# GND_PCB_Data_Conversion.net
KiCad netlist of a schematic drawn in Altium Designer
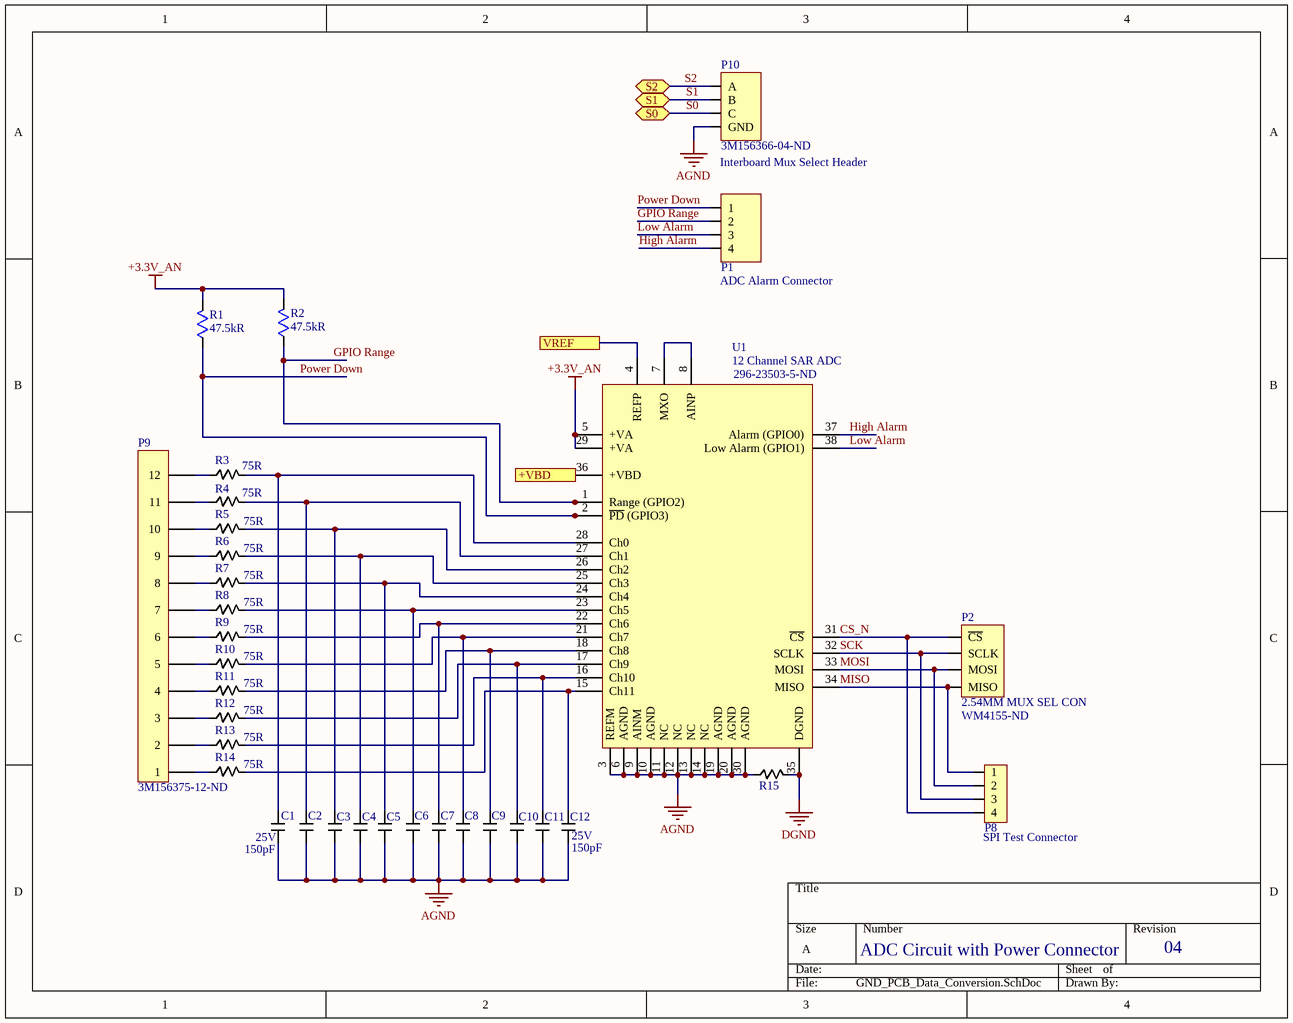
[diagram p0: GND_PCB_Data_Conversion.SchDoc]

(export (version "E")
  (design (tool "Eeschema 10.0.6"))
  (components
    (comp (ref "C1")
      (value "150PF Charge Res Caps")
      (footprint "150PF Cap Charge Resevoir")
      (description "Charge Res Caps for ADC input channels")
      (fields
        (field (name "MANUFACTURER") "KEMET")
        (field (name "MANUFACTURER PART NUMBER") "C0402C151J3GAC7867")
        (field (name "CAPACITANCE") "150pF")
        (field (name "VOLTAGE RATING") "25V")
      )
      (libsource (lib "Schematic_Library") (part "150PF Charge Res Caps"))
    )
    (comp (ref "C2")
      (value "150PF Charge Res Caps")
      (footprint "150PF Cap Charge Resevoir")
      (description "Charge Res Caps for ADC input channels")
      (fields
        (field (name "MANUFACTURER") "KEMET")
        (field (name "MANUFACTURER PART NUMBER") "C0402C151J3GAC7867")
      )
      (libsource (lib "Schematic_Library") (part "150PF Charge Res Caps"))
    )
    (comp (ref "C3")
      (value "150PF Charge Res Caps")
      (footprint "150PF Cap Charge Resevoir")
      (description "Charge Res Caps for ADC input channels")
      (fields
        (field (name "MANUFACTURER") "KEMET")
        (field (name "MANUFACTURER PART NUMBER") "C0402C151J3GAC7867")
      )
      (libsource (lib "Schematic_Library") (part "150PF Charge Res Caps"))
    )
    (comp (ref "C4")
      (value "150PF Charge Res Caps")
      (footprint "150PF Cap Charge Resevoir")
      (description "Charge Res Caps for ADC input channels")
      (fields
        (field (name "MANUFACTURER") "KEMET")
        (field (name "MANUFACTURER PART NUMBER") "C0402C151J3GAC7867")
      )
      (libsource (lib "Schematic_Library") (part "150PF Charge Res Caps"))
    )
    (comp (ref "C5")
      (value "150PF Charge Res Caps")
      (footprint "150PF Cap Charge Resevoir")
      (description "Charge Res Caps for ADC input channels")
      (fields
        (field (name "MANUFACTURER") "KEMET")
        (field (name "MANUFACTURER PART NUMBER") "C0402C151J3GAC7867")
      )
      (libsource (lib "Schematic_Library") (part "150PF Charge Res Caps"))
    )
    (comp (ref "C6")
      (value "150PF Charge Res Caps")
      (footprint "150PF Cap Charge Resevoir")
      (description "Charge Res Caps for ADC input channels")
      (fields
        (field (name "MANUFACTURER") "KEMET")
        (field (name "MANUFACTURER PART NUMBER") "C0402C151J3GAC7867")
      )
      (libsource (lib "Schematic_Library") (part "150PF Charge Res Caps"))
    )
    (comp (ref "C7")
      (value "150PF Charge Res Caps")
      (footprint "150PF Cap Charge Resevoir")
      (description "Charge Res Caps for ADC input channels")
      (fields
        (field (name "MANUFACTURER") "KEMET")
        (field (name "MANUFACTURER PART NUMBER") "C0402C151J3GAC7867")
      )
      (libsource (lib "Schematic_Library") (part "150PF Charge Res Caps"))
    )
    (comp (ref "C8")
      (value "150PF Charge Res Caps")
      (footprint "150PF Cap Charge Resevoir")
      (description "Charge Res Caps for ADC input channels")
      (fields
        (field (name "MANUFACTURER") "KEMET")
        (field (name "MANUFACTURER PART NUMBER") "C0402C151J3GAC7867")
      )
      (libsource (lib "Schematic_Library") (part "150PF Charge Res Caps"))
    )
    (comp (ref "C9")
      (value "150PF Charge Res Caps")
      (footprint "150PF Cap Charge Resevoir")
      (description "Charge Res Caps for ADC input channels")
      (fields
        (field (name "MANUFACTURER") "KEMET")
        (field (name "MANUFACTURER PART NUMBER") "C0402C151J3GAC7867")
      )
      (libsource (lib "Schematic_Library") (part "150PF Charge Res Caps"))
    )
    (comp (ref "C10")
      (value "150PF Charge Res Caps")
      (footprint "150PF Cap Charge Resevoir")
      (description "Charge Res Caps for ADC input channels")
      (fields
        (field (name "MANUFACTURER") "KEMET")
        (field (name "MANUFACTURER PART NUMBER") "C0402C151J3GAC7867")
      )
      (libsource (lib "Schematic_Library") (part "150PF Charge Res Caps"))
    )
    (comp (ref "C11")
      (value "150PF Charge Res Caps")
      (footprint "150PF Cap Charge Resevoir")
      (description "Charge Res Caps for ADC input channels")
      (fields
        (field (name "MANUFACTURER") "KEMET")
        (field (name "MANUFACTURER PART NUMBER") "C0402C151J3GAC7867")
      )
      (libsource (lib "Schematic_Library") (part "150PF Charge Res Caps"))
    )
    (comp (ref "C12")
      (value "150PF Charge Res Caps")
      (footprint "150PF Cap Charge Resevoir")
      (description "Charge Res Caps for ADC input channels")
      (fields
        (field (name "MANUFACTURER") "KEMET")
        (field (name "MANUFACTURER PART NUMBER") "C0402C151J3GAC7867")
        (field (name "CAPACITANCE") "150pF")
        (field (name "VOLTAGE RATING") "25V")
      )
      (libsource (lib "Schematic_Library") (part "150PF Charge Res Caps"))
    )
    (comp (ref "P1")
      (value "4 pos ADC Alarm Header")
      (footprint "4POS 2.54MM HEADER MUX SEL")
      (description "Connector Header Through Hole, Right Angle 4 position 0.100\" (2.54mm)")
      (fields (field (name "MANUFACTURER") "Molex") (field (name "MANUFACTURER PART NUMBER") "0705530108"))
      (libsource (lib "Schematic_Library") (part "4 pos ADC Alarm Header"))
    )
    (comp (ref "P2")
      (value "2.54MM MUX SEL CON")
      (footprint "4POS 2.54MM HEADER MUX SEL")
      (description "SPI Connector")
      (fields
        (field (name "MANUFACTURER") "Molex")
        (field (name "MANUFACTURER PART NUMBER") "0705530108")
        (field (name "SUPPLIER PART NUMBER 1") "WM4155-ND")
      )
      (libsource (lib "Schematic_Library") (part "2.54MM MUX SEL CON"))
    )
    (comp (ref "P8")
      (value "4POS SPI Test Connector Header Pin")
      (footprint "4POS SPI Test Connector")
      (description "Connector Header Through Hole, Right Angle 4 position 0.100\" (2.54mm)")
      (fields
        (field (name "MANUFACTURER") "TE Connectivity")
        (field (name "MANUFACTURER PART NUMBER") "640455-4")
      )
      (libsource (lib "Schematic_Library") (part "4POS SPI Test Connector Header Pin"))
    )
    (comp (ref "P9")
      (value "12POS Dual Header W/O 3D Body")
      (footprint "12POS Dual Header W/0 3D Body")
      (description "Connector Header Through Hole 12 position 0.100\" (2.54mm)")
      (fields
        (field (name "MANUFACTURER") "3M")
        (field (name "MANUFACTURER PART NUMBER") "929715-06-06-EU")
        (field (name "SUPPLIER PART NUMBER 1") "3M156375-12-ND")
      )
      (libsource (lib "Schematic_Library") (part "12POS Dual Header W/O 3D Body"))
    )
    (comp (ref "P10")
      (value "Mux Select Interboard Header")
      (footprint "Mux Select Interboard Connector")
      (description "Connector Header Through Hole 4 position 0.100\" (2.54mm)")
      (fields
        (field (name "MANUFACTURER") "3M")
        (field (name "MANUFACTURER PART NUMBER") "929710-06-02-RK")
        (field (name "SUPPLIER PART NUMBER 1") "3M156366-04-ND")
      )
      (libsource (lib "Schematic_Library") (part "Mux Select Interboard Header"))
    )
    (comp (ref "R1")
      (value "Green")
      (footprint "Green_LED_Resistor_90.9")
      (description "RES 47.5K OHM 0.5% 1/10W 0603")
      (fields
        (field (name "MANUFACTURER") "Stackpole Electronics")
        (field (name "MANUFACTURER PART NUMBER") "RNCF0603DTE47K5")
        (field (name "RESISTANCE") "47.5kR")
      )
      (libsource (lib "Schematic_Library") (part "47.5k PullUp RES ADC"))
    )
    (comp (ref "R2")
      (value "47.5k PullUp RES ADC")
      (footprint "0603_MD_RES")
      (description "RES 47.5K OHM 0.5% 1/10W 0603")
      (fields
        (field (name "MANUFACTURER") "Stackpole Electronics")
        (field (name "MANUFACTURER PART NUMBER") "RNCF0603DTE47K5")
        (field (name "RESISTANCE") "47.5kR")
      )
      (libsource (lib "Schematic_Library") (part "47.5k PullUp RES ADC"))
    )
    (comp (ref "R3")
      (value "75 Ohm Charge Resevoir Resistor")
      (footprint "Chip2PinSM127P600-8N")
      (fields
        (field (name "MANUFACTURER") "Rohm")
        (field (name "MANUFACTURER PART NUMBER") "KTR03EZPF75R0")
        (field (name "TOLERANCE") "1%")
        (field (name "RESISTANCE") "75R")
      )
      (libsource (lib "Schematic_Library") (part "75 Ohm Charge Resevoir Resistor"))
    )
    (comp (ref "R4")
      (value "75 Ohm Charge Resevoir Resistor")
      (footprint "Chip2PinSM127P600-8N")
      (fields
        (field (name "MANUFACTURER") "Rohm")
        (field (name "MANUFACTURER PART NUMBER") "KTR03EZPF75R0")
        (field (name "TOLERANCE") "1%")
        (field (name "RESISTANCE") "75R")
      )
      (libsource (lib "Schematic_Library") (part "75 Ohm Charge Resevoir Resistor"))
    )
    (comp (ref "R5")
      (value "75 Ohm Charge Resevoir Resistor")
      (footprint "Chip2PinSM127P600-8N")
      (fields
        (field (name "MANUFACTURER") "Rohm")
        (field (name "MANUFACTURER PART NUMBER") "KTR03EZPF75R0")
        (field (name "TOLERANCE") "1%")
        (field (name "RESISTANCE") "75R")
      )
      (libsource (lib "Schematic_Library") (part "75 Ohm Charge Resevoir Resistor"))
    )
    (comp (ref "R6")
      (value "75 Ohm Charge Resevoir Resistor")
      (footprint "Chip2PinSM127P600-8N")
      (fields
        (field (name "MANUFACTURER") "Rohm")
        (field (name "MANUFACTURER PART NUMBER") "KTR03EZPF75R0")
        (field (name "TOLERANCE") "1%")
        (field (name "RESISTANCE") "75R")
      )
      (libsource (lib "Schematic_Library") (part "75 Ohm Charge Resevoir Resistor"))
    )
    (comp (ref "R7")
      (value "75 Ohm Charge Resevoir Resistor")
      (footprint "Chip2PinSM127P600-8N")
      (fields
        (field (name "MANUFACTURER") "Rohm")
        (field (name "MANUFACTURER PART NUMBER") "KTR03EZPF75R0")
        (field (name "TOLERANCE") "1%")
        (field (name "RESISTANCE") "75R")
      )
      (libsource (lib "Schematic_Library") (part "75 Ohm Charge Resevoir Resistor"))
    )
    (comp (ref "R8")
      (value "75 Ohm Charge Resevoir Resistor")
      (footprint "Chip2PinSM127P600-8N")
      (fields
        (field (name "MANUFACTURER") "Rohm")
        (field (name "MANUFACTURER PART NUMBER") "KTR03EZPF75R0")
        (field (name "TOLERANCE") "1%")
        (field (name "RESISTANCE") "75R")
      )
      (libsource (lib "Schematic_Library") (part "75 Ohm Charge Resevoir Resistor"))
    )
    (comp (ref "R9")
      (value "75 Ohm Charge Resevoir Resistor")
      (footprint "Chip2PinSM127P600-8N")
      (fields
        (field (name "MANUFACTURER") "Rohm")
        (field (name "MANUFACTURER PART NUMBER") "KTR03EZPF75R0")
        (field (name "TOLERANCE") "1%")
        (field (name "RESISTANCE") "75R")
      )
      (libsource (lib "Schematic_Library") (part "75 Ohm Charge Resevoir Resistor"))
    )
    (comp (ref "R10")
      (value "75 Ohm Charge Resevoir Resistor")
      (footprint "Chip2PinSM127P600-8N")
      (fields
        (field (name "MANUFACTURER") "Rohm")
        (field (name "MANUFACTURER PART NUMBER") "KTR03EZPF75R0")
        (field (name "TOLERANCE") "1%")
        (field (name "RESISTANCE") "75R")
      )
      (libsource (lib "Schematic_Library") (part "75 Ohm Charge Resevoir Resistor"))
    )
    (comp (ref "R11")
      (value "75 Ohm Charge Resevoir Resistor")
      (footprint "Chip2PinSM127P600-8N")
      (fields
        (field (name "MANUFACTURER") "Rohm")
        (field (name "MANUFACTURER PART NUMBER") "KTR03EZPF75R0")
        (field (name "TOLERANCE") "1%")
        (field (name "RESISTANCE") "75R")
      )
      (libsource (lib "Schematic_Library") (part "75 Ohm Charge Resevoir Resistor"))
    )
    (comp (ref "R12")
      (value "75 Ohm Charge Resevoir Resistor")
      (footprint "Chip2PinSM127P600-8N")
      (fields
        (field (name "MANUFACTURER") "Rohm")
        (field (name "MANUFACTURER PART NUMBER") "KTR03EZPF75R0")
        (field (name "TOLERANCE") "1%")
        (field (name "RESISTANCE") "75R")
      )
      (libsource (lib "Schematic_Library") (part "75 Ohm Charge Resevoir Resistor"))
    )
    (comp (ref "R13")
      (value "75 Ohm Charge Resevoir Resistor")
      (footprint "Chip2PinSM127P600-8N")
      (fields
        (field (name "MANUFACTURER") "Rohm")
        (field (name "MANUFACTURER PART NUMBER") "KTR03EZPF75R0")
        (field (name "TOLERANCE") "1%")
        (field (name "RESISTANCE") "75R")
      )
      (libsource (lib "Schematic_Library") (part "75 Ohm Charge Resevoir Resistor"))
    )
    (comp (ref "R14")
      (value "75 Ohm Charge Resevoir Resistor")
      (footprint "Chip2PinSM127P600-8N")
      (fields
        (field (name "MANUFACTURER") "Rohm")
        (field (name "MANUFACTURER PART NUMBER") "KTR03EZPF75R0")
        (field (name "TOLERANCE") "1%")
        (field (name "RESISTANCE") "75R")
      )
      (libsource (lib "Schematic_Library") (part "75 Ohm Charge Resevoir Resistor"))
    )
    (comp (ref "R15")
      (value "0 Ohm Resistor")
      (footprint "0 Ohm Resistor")
      (description "0 Ohm Resistor for connecting polygon pours")
      (libsource (lib "Schematic_Library") (part "0 Ohm Resistor"))
    )
    (comp (ref "U1")
      (value "12 Channel SAR ADC")
      (footprint "12 Channel SAR ADC")
      (description "12 Bit SAR ADC")
      (fields
        (field (name "MANUFACTURER") "Texas Instruments")
        (field (name "MANUFACTURER PART NUMBER") "ADS7952SDBT")
        (field (name "SUPPLIER PART NUMBER 1") "296-23503-5-ND")
      )
      (libsource (lib "Schematic_Library") (part "12 Channel SAR ADC"))
    )
  )
  (nets
    (net (code "1") (name "+3.3V_AN") (class "Default")
      (node (ref "R1") (pin "2") (pinfunction "2_2") (pintype "passive"))
      (node (ref "R2") (pin "2") (pinfunction "2_2") (pintype "passive"))
      (node (ref "U1") (pin "29") (pinfunction "+VA_29") (pintype "passive"))
      (node (ref "U1") (pin "5") (pinfunction "+VA_5") (pintype "passive"))
    )
    (net (code "2") (name "/+VBD") (class "Default")
      (node (ref "U1") (pin "36") (pinfunction "+VBD_36") (pintype "passive"))
    )
    (net (code "3") (name "/CS_N") (class "Default")
      (node (ref "P2") (pin "4") (pinfunction "~{CS}_4") (pintype "passive"))
      (node (ref "P8") (pin "4") (pinfunction "4_4") (pintype "passive"))
      (node (ref "U1") (pin "31") (pinfunction "~{CS}_31") (pintype "passive"))
    )
    (net (code "4") (name "/GPIO Range") (class "Default")
      (node (ref "P1") (pin "2") (pinfunction "2_2") (pintype "passive"))
      (node (ref "R2") (pin "1") (pinfunction "1_1") (pintype "passive"))
      (node (ref "U1") (pin "1") (pinfunction "Range_(GPIO2)_1") (pintype "passive"))
    )
    (net (code "5") (name "/High Alarm") (class "Default")
      (node (ref "P1") (pin "4") (pinfunction "4_4") (pintype "passive"))
      (node (ref "U1") (pin "37") (pinfunction "Alarm_(GPIO0)_37") (pintype "passive"))
    )
    (net (code "6") (name "/Low Alarm") (class "Default")
      (node (ref "P1") (pin "3") (pinfunction "3_3") (pintype "passive"))
      (node (ref "U1") (pin "38") (pinfunction "Low_Alarm_(GPIO1)_38") (pintype "passive"))
    )
    (net (code "7") (name "/MISO") (class "Default")
      (node (ref "P2") (pin "1") (pinfunction "MISO_1") (pintype "passive"))
      (node (ref "P8") (pin "1") (pinfunction "1_1") (pintype "passive"))
      (node (ref "U1") (pin "34") (pinfunction "MISO_34") (pintype "passive"))
    )
    (net (code "8") (name "/MOSI") (class "Default")
      (node (ref "P2") (pin "2") (pinfunction "MOSI_2") (pintype "passive"))
      (node (ref "P8") (pin "2") (pinfunction "2_2") (pintype "passive"))
      (node (ref "U1") (pin "33") (pinfunction "MOSI_33") (pintype "passive"))
    )
    (net (code "9") (name "/Power Down") (class "Default")
      (node (ref "P1") (pin "1") (pinfunction "1_1") (pintype "passive"))
      (node (ref "R1") (pin "1") (pinfunction "1_1") (pintype "passive"))
      (node (ref "U1") (pin "2") (pinfunction "~{PD}_(GPIO3)_2") (pintype "passive"))
    )
    (net (code "10") (name "/S0") (class "Default")
      (node (ref "P10") (pin "3") (pinfunction "C_3") (pintype "passive"))
    )
    (net (code "11") (name "/S1") (class "Default")
      (node (ref "P10") (pin "2") (pinfunction "B_2") (pintype "passive"))
    )
    (net (code "12") (name "/S2") (class "Default")
      (node (ref "P10") (pin "1") (pinfunction "A_1") (pintype "passive"))
    )
    (net (code "13") (name "/SCK") (class "Default")
      (node (ref "P2") (pin "3") (pinfunction "SCLK_3") (pintype "passive"))
      (node (ref "P8") (pin "3") (pinfunction "3_3") (pintype "passive"))
      (node (ref "U1") (pin "32") (pinfunction "SCLK_32") (pintype "passive"))
    )
    (net (code "14") (name "/VREF") (class "Default")
      (node (ref "U1") (pin "4") (pinfunction "REFP_4") (pintype "passive"))
    )
    (net (code "15") (name "AGND") (class "Default")
      (node (ref "C1") (pin "1") (pinfunction "1_1") (pintype "passive"))
      (node (ref "C10") (pin "1") (pinfunction "1_1") (pintype "passive"))
      (node (ref "C11") (pin "1") (pinfunction "1_1") (pintype "passive"))
      (node (ref "C12") (pin "1") (pinfunction "1_1") (pintype "passive"))
      (node (ref "C2") (pin "1") (pinfunction "1_1") (pintype "passive"))
      (node (ref "C3") (pin "1") (pinfunction "1_1") (pintype "passive"))
      (node (ref "C4") (pin "1") (pinfunction "1_1") (pintype "passive"))
      (node (ref "C5") (pin "1") (pinfunction "1_1") (pintype "passive"))
      (node (ref "C6") (pin "1") (pinfunction "1_1") (pintype "passive"))
      (node (ref "C7") (pin "1") (pinfunction "1_1") (pintype "passive"))
      (node (ref "C8") (pin "1") (pinfunction "1_1") (pintype "passive"))
      (node (ref "C9") (pin "1") (pinfunction "1_1") (pintype "passive"))
      (node (ref "P10") (pin "4") (pinfunction "GND_4") (pintype "passive"))
      (node (ref "R15") (pin "1") (pinfunction "1_1") (pintype "passive"))
      (node (ref "U1") (pin "10") (pinfunction "AGND_10") (pintype "passive"))
      (node (ref "U1") (pin "11") (pinfunction "NC_11") (pintype "passive"))
      (node (ref "U1") (pin "12") (pinfunction "NC_12") (pintype "passive"))
      (node (ref "U1") (pin "13") (pinfunction "NC_13") (pintype "passive"))
      (node (ref "U1") (pin "14") (pinfunction "NC_14") (pintype "passive"))
      (node (ref "U1") (pin "19") (pinfunction "AGND_19") (pintype "passive"))
      (node (ref "U1") (pin "20") (pinfunction "AGND_20") (pintype "passive"))
      (node (ref "U1") (pin "3") (pinfunction "REFM_3") (pintype "passive"))
      (node (ref "U1") (pin "30") (pinfunction "AGND_30") (pintype "passive"))
      (node (ref "U1") (pin "6") (pinfunction "AGND_6") (pintype "passive"))
      (node (ref "U1") (pin "9") (pinfunction "AINM_9") (pintype "passive"))
    )
    (net (code "16") (name "DGND") (class "Default")
      (node (ref "R15") (pin "2") (pinfunction "2_2") (pintype "passive"))
      (node (ref "U1") (pin "35") (pinfunction "DGND_35") (pintype "passive"))
    )
    (net (code "17") (name "Net-(P9-Pad1)") (class "Default")
      (node (ref "P9") (pin "1") (pinfunction "1_1") (pintype "passive"))
      (node (ref "R14") (pin "1") (pinfunction "1_1") (pintype "passive"))
    )
    (net (code "18") (name "Net-(P9-Pad2)") (class "Default")
      (node (ref "P9") (pin "2") (pinfunction "2_2") (pintype "passive"))
      (node (ref "R13") (pin "1") (pinfunction "1_1") (pintype "passive"))
    )
    (net (code "19") (name "Net-(P9-Pad3)") (class "Default")
      (node (ref "P9") (pin "3") (pinfunction "3_3") (pintype "passive"))
      (node (ref "R12") (pin "1") (pinfunction "1_1") (pintype "passive"))
    )
    (net (code "20") (name "Net-(P9-Pad4)") (class "Default")
      (node (ref "P9") (pin "4") (pinfunction "4_4") (pintype "passive"))
      (node (ref "R11") (pin "1") (pinfunction "1_1") (pintype "passive"))
    )
    (net (code "21") (name "Net-(P9-Pad5)") (class "Default")
      (node (ref "P9") (pin "5") (pinfunction "5_5") (pintype "passive"))
      (node (ref "R10") (pin "1") (pinfunction "1_1") (pintype "passive"))
    )
    (net (code "22") (name "Net-(P9-Pad6)") (class "Default")
      (node (ref "P9") (pin "6") (pinfunction "6_6") (pintype "passive"))
      (node (ref "R9") (pin "1") (pinfunction "1_1") (pintype "passive"))
    )
    (net (code "23") (name "Net-(P9-Pad7)") (class "Default")
      (node (ref "P9") (pin "7") (pinfunction "7_7") (pintype "passive"))
      (node (ref "R8") (pin "1") (pinfunction "1_1") (pintype "passive"))
    )
    (net (code "24") (name "Net-(P9-Pad8)") (class "Default")
      (node (ref "P9") (pin "8") (pinfunction "8_8") (pintype "passive"))
      (node (ref "R7") (pin "1") (pinfunction "1_1") (pintype "passive"))
    )
    (net (code "25") (name "Net-(P9-Pad9)") (class "Default")
      (node (ref "P9") (pin "9") (pinfunction "9_9") (pintype "passive"))
      (node (ref "R6") (pin "1") (pinfunction "1_1") (pintype "passive"))
    )
    (net (code "26") (name "Net-(P9-Pad10)") (class "Default")
      (node (ref "P9") (pin "10") (pinfunction "10_10") (pintype "passive"))
      (node (ref "R5") (pin "1") (pinfunction "1_1") (pintype "passive"))
    )
    (net (code "27") (name "Net-(P9-Pad11)") (class "Default")
      (node (ref "P9") (pin "11") (pinfunction "11_11") (pintype "passive"))
      (node (ref "R4") (pin "1") (pinfunction "1_1") (pintype "passive"))
    )
    (net (code "28") (name "Net-(P9-Pad12)") (class "Default")
      (node (ref "P9") (pin "12") (pinfunction "12_12") (pintype "passive"))
      (node (ref "R3") (pin "1") (pinfunction "1_1") (pintype "passive"))
    )
    (net (code "29") (name "Net-(U1-AINP)") (class "Default")
      (node (ref "U1") (pin "7") (pinfunction "MXO_7") (pintype "passive"))
      (node (ref "U1") (pin "8") (pinfunction "AINP_8") (pintype "passive"))
    )
    (net (code "30") (name "Net-(U1-Ch0)") (class "Default")
      (node (ref "C1") (pin "2") (pinfunction "2_2") (pintype "passive"))
      (node (ref "R3") (pin "2") (pinfunction "2_2") (pintype "passive"))
      (node (ref "U1") (pin "28") (pinfunction "Ch0_28") (pintype "passive"))
    )
    (net (code "31") (name "Net-(U1-Ch1)") (class "Default")
      (node (ref "C2") (pin "2") (pinfunction "2_2") (pintype "passive"))
      (node (ref "R4") (pin "2") (pinfunction "2_2") (pintype "passive"))
      (node (ref "U1") (pin "27") (pinfunction "Ch1_27") (pintype "passive"))
    )
    (net (code "32") (name "Net-(U1-Ch2)") (class "Default")
      (node (ref "C3") (pin "2") (pinfunction "2_2") (pintype "passive"))
      (node (ref "R5") (pin "2") (pinfunction "2_2") (pintype "passive"))
      (node (ref "U1") (pin "26") (pinfunction "Ch2_26") (pintype "passive"))
    )
    (net (code "33") (name "Net-(U1-Ch3)") (class "Default")
      (node (ref "C4") (pin "2") (pinfunction "2_2") (pintype "passive"))
      (node (ref "R6") (pin "2") (pinfunction "2_2") (pintype "passive"))
      (node (ref "U1") (pin "25") (pinfunction "Ch3_25") (pintype "passive"))
    )
    (net (code "34") (name "Net-(U1-Ch4)") (class "Default")
      (node (ref "C5") (pin "2") (pinfunction "2_2") (pintype "passive"))
      (node (ref "R7") (pin "2") (pinfunction "2_2") (pintype "passive"))
      (node (ref "U1") (pin "24") (pinfunction "Ch4_24") (pintype "passive"))
    )
    (net (code "35") (name "Net-(U1-Ch5)") (class "Default")
      (node (ref "C6") (pin "2") (pinfunction "2_2") (pintype "passive"))
      (node (ref "R8") (pin "2") (pinfunction "2_2") (pintype "passive"))
      (node (ref "U1") (pin "23") (pinfunction "Ch5_23") (pintype "passive"))
    )
    (net (code "36") (name "Net-(U1-Ch6)") (class "Default")
      (node (ref "C7") (pin "2") (pinfunction "2_2") (pintype "passive"))
      (node (ref "R9") (pin "2") (pinfunction "2_2") (pintype "passive"))
      (node (ref "U1") (pin "22") (pinfunction "Ch6_22") (pintype "passive"))
    )
    (net (code "37") (name "Net-(U1-Ch7)") (class "Default")
      (node (ref "C8") (pin "2") (pinfunction "2_2") (pintype "passive"))
      (node (ref "R10") (pin "2") (pinfunction "2_2") (pintype "passive"))
      (node (ref "U1") (pin "21") (pinfunction "Ch7_21") (pintype "passive"))
    )
    (net (code "38") (name "Net-(U1-Ch8)") (class "Default")
      (node (ref "C9") (pin "2") (pinfunction "2_2") (pintype "passive"))
      (node (ref "R11") (pin "2") (pinfunction "2_2") (pintype "passive"))
      (node (ref "U1") (pin "18") (pinfunction "Ch8_18") (pintype "passive"))
    )
    (net (code "39") (name "Net-(U1-Ch9)") (class "Default")
      (node (ref "C10") (pin "2") (pinfunction "2_2") (pintype "passive"))
      (node (ref "R12") (pin "2") (pinfunction "2_2") (pintype "passive"))
      (node (ref "U1") (pin "17") (pinfunction "Ch9_17") (pintype "passive"))
    )
    (net (code "40") (name "Net-(U1-Ch10)") (class "Default")
      (node (ref "C11") (pin "2") (pinfunction "2_2") (pintype "passive"))
      (node (ref "R13") (pin "2") (pinfunction "2_2") (pintype "passive"))
      (node (ref "U1") (pin "16") (pinfunction "Ch10_16") (pintype "passive"))
    )
    (net (code "41") (name "Net-(U1-Ch11)") (class "Default")
      (node (ref "C12") (pin "2") (pinfunction "2_2") (pintype "passive"))
      (node (ref "R14") (pin "2") (pinfunction "2_2") (pintype "passive"))
      (node (ref "U1") (pin "15") (pinfunction "Ch11_15") (pintype "passive"))
    )
  )
)
